# SCH_Bluetonium-canister_2024-05-14.net
KiCad netlist of a schematic drawn in EasyEDA
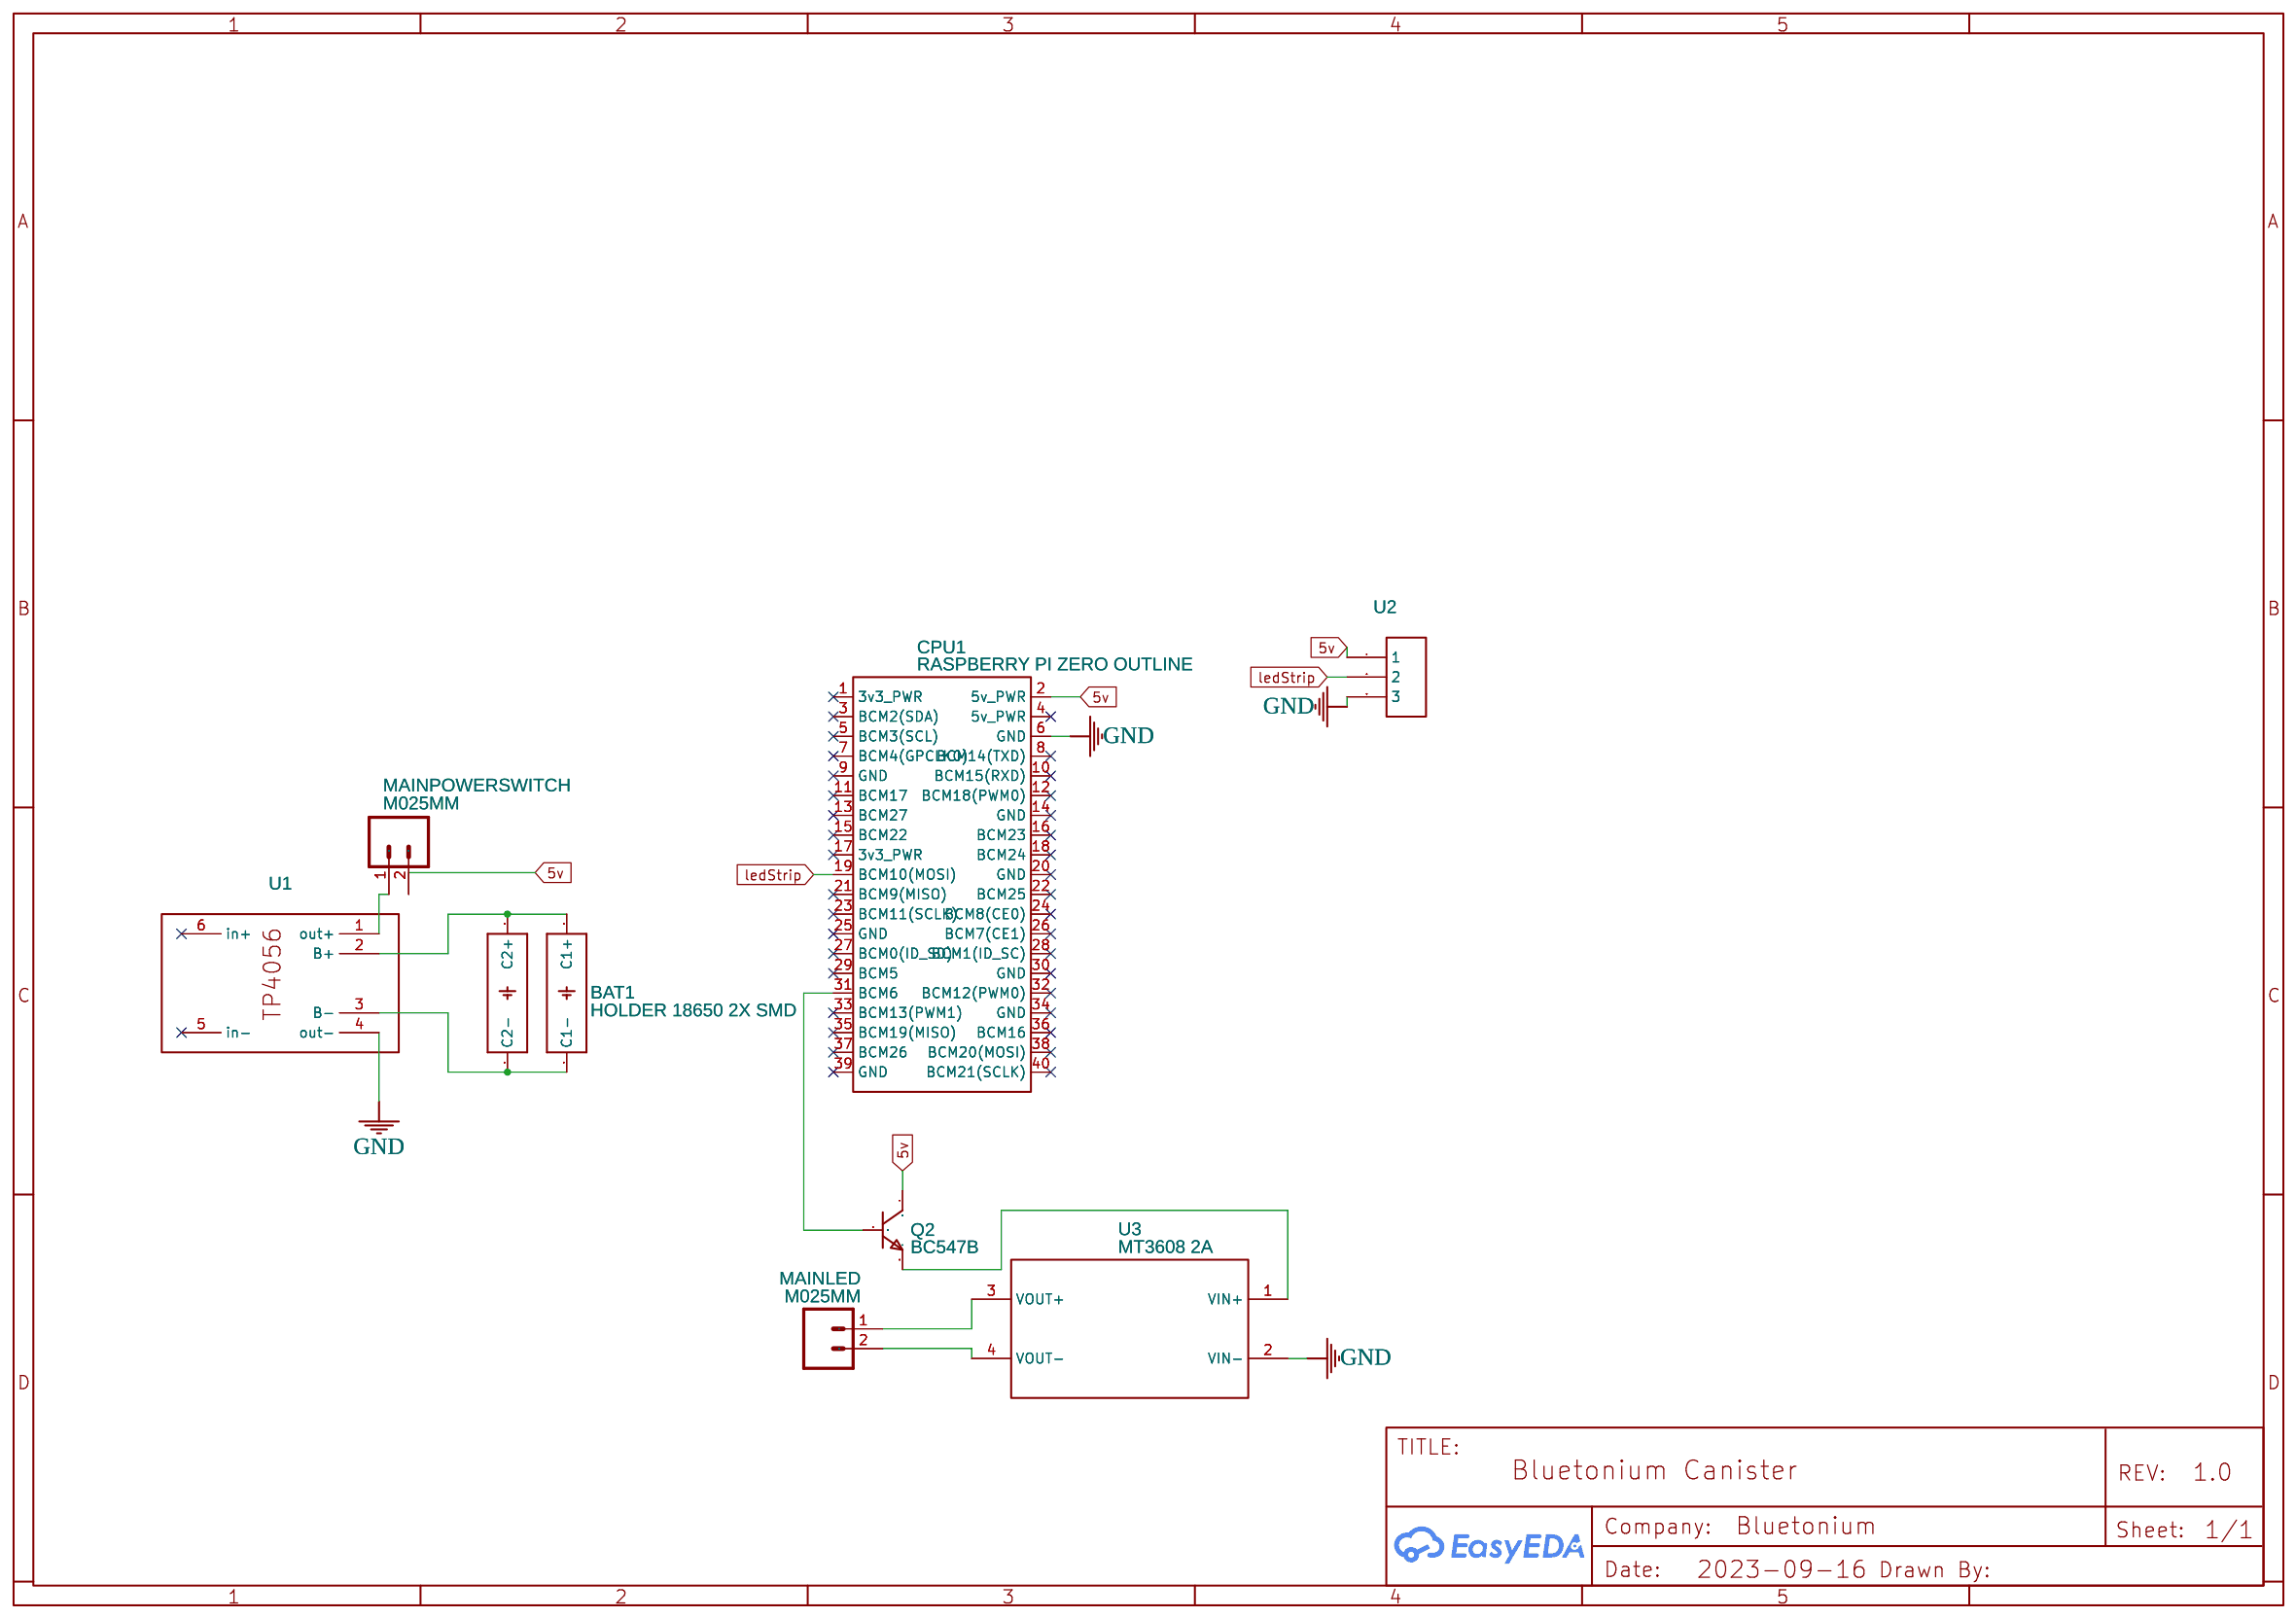
[diagram p0: schematic sheet]

(export (version "E")
  (design (tool "Eeschema 10.0.6"))
  (components
    (comp (ref "BAT1") (value "HOLDER 18650 2X SMD") (libsource (lib "") (part "HOLDER 18650 2X SMD")))
    (comp (ref "CPU1")
      (value "RASPBERRY PI ZERO OUTLINE")
      (fields (field (name "Manufacturer Part") "Pi Zero W") (field (name "Manufacturer") "Raspberry Pi"))
      (libsource (lib "") (part "RASPBERRY PI ZERO OUTLINE"))
    )
    (comp (ref "MAINLED") (value "M025MM") (libsource (lib "") (part "M025MM")))
    (comp (ref "MAINPOWERSWITCH") (value "M025MM") (libsource (lib "") (part "M025MM_1")))
    (comp (ref "Q2")
      (value "BC547B")
      (fields (field (name "Manufacturer") "MULTICOMP"))
      (libsource (lib "") (part "BC547B"))
    )
    (comp (ref "U1") (value "NO") (libsource (lib "") (part "TP4056")))
    (comp (ref "U2") (value "NO") (libsource (lib "") (part "PORT-3PIN-P2.54")))
    (comp (ref "U3")
      (value "MT3608 2A")
      (fields (field (name "Manufacturer Part") "mt3608-1"))
      (libsource (lib "") (part "MT3608 2A"))
    )
  )
  (nets
    (net (code "1") (name "5v") (class "Default")
      (node (ref "CPU1") (pin "2") (pinfunction "5v_PWR_2") (pintype "unspecified"))
      (node (ref "MAINPOWERSWITCH") (pin "2") (pinfunction "2_2") (pintype "bidirectional"))
      (node (ref "Q2") (pin "1") (pinfunction "C_1") (pintype "unspecified"))
      (node (ref "U2") (pin "1") (pinfunction "1_1") (pintype "unspecified"))
    )
    (net (code "2") (name "GND") (class "Default")
      (node (ref "CPU1") (pin "6") (pinfunction "GND_6") (pintype "unspecified"))
      (node (ref "U1") (pin "4") (pinfunction "out-_4") (pintype "unspecified"))
      (node (ref "U2") (pin "3") (pinfunction "3_3") (pintype "unspecified"))
      (node (ref "U3") (pin "2") (pinfunction "VIN-_2") (pintype "unspecified"))
    )
    (net (code "3") (name "Net-(BAT1-C1+)") (class "Default")
      (node (ref "BAT1") (pin "1+") (pinfunction "C1+_1+") (pintype "bidirectional"))
      (node (ref "BAT1") (pin "2+") (pinfunction "C2+_2+") (pintype "bidirectional"))
      (node (ref "U1") (pin "2") (pinfunction "B+_2") (pintype "unspecified"))
    )
    (net (code "4") (name "Net-(BAT1-C1-)") (class "Default")
      (node (ref "BAT1") (pin "1-") (pinfunction "C1-_1-") (pintype "bidirectional"))
      (node (ref "BAT1") (pin "2-") (pinfunction "C2-_2-") (pintype "bidirectional"))
      (node (ref "U1") (pin "3") (pinfunction "B-_3") (pintype "unspecified"))
    )
    (net (code "5") (name "Net-(CPU1-BCM6)") (class "Default")
      (node (ref "CPU1") (pin "31") (pinfunction "BCM6_31") (pintype "unspecified"))
      (node (ref "Q2") (pin "2") (pinfunction "B_2") (pintype "unspecified"))
    )
    (net (code "6") (name "Net-(Q2-E)") (class "Default")
      (node (ref "Q2") (pin "3") (pinfunction "E_3") (pintype "unspecified"))
      (node (ref "U3") (pin "1") (pinfunction "VIN+_1") (pintype "unspecified"))
    )
    (net (code "7") (name "Net-(U1-out+)") (class "Default")
      (node (ref "MAINPOWERSWITCH") (pin "1") (pinfunction "1_1") (pintype "bidirectional"))
      (node (ref "U1") (pin "1") (pinfunction "out+_1") (pintype "unspecified"))
    )
    (net (code "8") (name "Net-(U3-VOUT+)") (class "Default")
      (node (ref "MAINLED") (pin "1") (pinfunction "1_1") (pintype "bidirectional"))
      (node (ref "U3") (pin "3") (pinfunction "VOUT+_3") (pintype "unspecified"))
    )
    (net (code "9") (name "Net-(U3-VOUT-)") (class "Default")
      (node (ref "MAINLED") (pin "2") (pinfunction "2_2") (pintype "bidirectional"))
      (node (ref "U3") (pin "4") (pinfunction "VOUT-_4") (pintype "unspecified"))
    )
    (net (code "10") (name "ledStrip") (class "Default")
      (node (ref "CPU1") (pin "19") (pinfunction "BCM10(MOSI)_19") (pintype "unspecified"))
      (node (ref "U2") (pin "2") (pinfunction "2_2") (pintype "unspecified"))
    )
    (net (code "11") (name "unconnected-(CPU1-3v3_PWR-Pad1)") (class "Default")
      (node (ref "CPU1") (pin "1") (pinfunction "3v3_PWR_1") (pintype "passive+no_connect"))
    )
    (net (code "12") (name "unconnected-(CPU1-3v3_PWR-Pad17)") (class "Default")
      (node (ref "CPU1") (pin "17") (pinfunction "3v3_PWR_17") (pintype "unspecified+no_connect"))
    )
    (net (code "13") (name "unconnected-(CPU1-5v_PWR-Pad4)") (class "Default")
      (node (ref "CPU1") (pin "4") (pinfunction "5v_PWR_4") (pintype "unspecified+no_connect"))
    )
    (net (code "14") (name "unconnected-(CPU1-BCM0(ID_SD)-Pad27)") (class "Default")
      (node (ref "CPU1") (pin "27") (pinfunction "BCM0(ID_SD)_27") (pintype "unspecified+no_connect"))
    )
    (net (code "15") (name "unconnected-(CPU1-BCM1(ID_SC)-Pad28)") (class "Default")
      (node (ref "CPU1") (pin "28") (pinfunction "BCM1(ID_SC)_28") (pintype "unspecified+no_connect"))
    )
    (net (code "16") (name "unconnected-(CPU1-BCM2(SDA)-Pad3)") (class "Default")
      (node (ref "CPU1") (pin "3") (pinfunction "BCM2(SDA)_3") (pintype "unspecified+no_connect"))
    )
    (net (code "17") (name "unconnected-(CPU1-BCM3(SCL)-Pad5)") (class "Default")
      (node (ref "CPU1") (pin "5") (pinfunction "BCM3(SCL)_5") (pintype "unspecified+no_connect"))
    )
    (net (code "18") (name "unconnected-(CPU1-BCM4(GPCLK0)-Pad7)") (class "Default")
      (node (ref "CPU1") (pin "7") (pinfunction "BCM4(GPCLK0)_7") (pintype "unspecified+no_connect"))
    )
    (net (code "19") (name "unconnected-(CPU1-BCM5-Pad29)") (class "Default")
      (node (ref "CPU1") (pin "29") (pinfunction "BCM5_29") (pintype "unspecified+no_connect"))
    )
    (net (code "20") (name "unconnected-(CPU1-BCM7(CE1)-Pad26)") (class "Default")
      (node (ref "CPU1") (pin "26") (pinfunction "BCM7(CE1)_26") (pintype "unspecified+no_connect"))
    )
    (net (code "21") (name "unconnected-(CPU1-BCM8(CE0)-Pad24)") (class "Default")
      (node (ref "CPU1") (pin "24") (pinfunction "BCM8(CE0)_24") (pintype "unspecified+no_connect"))
    )
    (net (code "22") (name "unconnected-(CPU1-BCM9(MISO)-Pad21)") (class "Default")
      (node (ref "CPU1") (pin "21") (pinfunction "BCM9(MISO)_21") (pintype "unspecified+no_connect"))
    )
    (net (code "23") (name "unconnected-(CPU1-BCM11(SCLK)-Pad23)") (class "Default")
      (node (ref "CPU1") (pin "23") (pinfunction "BCM11(SCLK)_23") (pintype "unspecified+no_connect"))
    )
    (net (code "24") (name "unconnected-(CPU1-BCM12(PWM0)-Pad32)") (class "Default")
      (node (ref "CPU1") (pin "32") (pinfunction "BCM12(PWM0)_32") (pintype "unspecified+no_connect"))
    )
    (net (code "25") (name "unconnected-(CPU1-BCM13(PWM1)-Pad33)") (class "Default")
      (node (ref "CPU1") (pin "33") (pinfunction "BCM13(PWM1)_33") (pintype "unspecified+no_connect"))
    )
    (net (code "26") (name "unconnected-(CPU1-BCM14(TXD)-Pad8)") (class "Default")
      (node (ref "CPU1") (pin "8") (pinfunction "BCM14(TXD)_8") (pintype "unspecified+no_connect"))
    )
    (net (code "27") (name "unconnected-(CPU1-BCM15(RXD)-Pad10)") (class "Default")
      (node (ref "CPU1") (pin "10") (pinfunction "BCM15(RXD)_10") (pintype "unspecified+no_connect"))
    )
    (net (code "28") (name "unconnected-(CPU1-BCM16-Pad36)") (class "Default")
      (node (ref "CPU1") (pin "36") (pinfunction "BCM16_36") (pintype "unspecified+no_connect"))
    )
    (net (code "29") (name "unconnected-(CPU1-BCM17-Pad11)") (class "Default")
      (node (ref "CPU1") (pin "11") (pinfunction "BCM17_11") (pintype "unspecified+no_connect"))
    )
    (net (code "30") (name "unconnected-(CPU1-BCM18(PWM0)-Pad12)") (class "Default")
      (node (ref "CPU1") (pin "12") (pinfunction "BCM18(PWM0)_12") (pintype "unspecified+no_connect"))
    )
    (net (code "31") (name "unconnected-(CPU1-BCM19(MISO)-Pad35)") (class "Default")
      (node (ref "CPU1") (pin "35") (pinfunction "BCM19(MISO)_35") (pintype "unspecified+no_connect"))
    )
    (net (code "32") (name "unconnected-(CPU1-BCM20(MOSI)-Pad38)") (class "Default")
      (node (ref "CPU1") (pin "38") (pinfunction "BCM20(MOSI)_38") (pintype "unspecified+no_connect"))
    )
    (net (code "33") (name "unconnected-(CPU1-BCM21(SCLK)-Pad40)") (class "Default")
      (node (ref "CPU1") (pin "40") (pinfunction "BCM21(SCLK)_40") (pintype "unspecified+no_connect"))
    )
    (net (code "34") (name "unconnected-(CPU1-BCM22-Pad15)") (class "Default")
      (node (ref "CPU1") (pin "15") (pinfunction "BCM22_15") (pintype "unspecified+no_connect"))
    )
    (net (code "35") (name "unconnected-(CPU1-BCM23-Pad16)") (class "Default")
      (node (ref "CPU1") (pin "16") (pinfunction "BCM23_16") (pintype "unspecified+no_connect"))
    )
    (net (code "36") (name "unconnected-(CPU1-BCM24-Pad18)") (class "Default")
      (node (ref "CPU1") (pin "18") (pinfunction "BCM24_18") (pintype "unspecified+no_connect"))
    )
    (net (code "37") (name "unconnected-(CPU1-BCM25-Pad22)") (class "Default")
      (node (ref "CPU1") (pin "22") (pinfunction "BCM25_22") (pintype "unspecified+no_connect"))
    )
    (net (code "38") (name "unconnected-(CPU1-BCM26-Pad37)") (class "Default")
      (node (ref "CPU1") (pin "37") (pinfunction "BCM26_37") (pintype "unspecified+no_connect"))
    )
    (net (code "39") (name "unconnected-(CPU1-BCM27-Pad13)") (class "Default")
      (node (ref "CPU1") (pin "13") (pinfunction "BCM27_13") (pintype "unspecified+no_connect"))
    )
    (net (code "40") (name "unconnected-(CPU1-GND-Pad9)") (class "Default")
      (node (ref "CPU1") (pin "9") (pinfunction "GND_9") (pintype "unspecified+no_connect"))
    )
    (net (code "41") (name "unconnected-(CPU1-GND-Pad14)") (class "Default")
      (node (ref "CPU1") (pin "14") (pinfunction "GND_14") (pintype "unspecified+no_connect"))
    )
    (net (code "42") (name "unconnected-(CPU1-GND-Pad20)") (class "Default")
      (node (ref "CPU1") (pin "20") (pinfunction "GND_20") (pintype "unspecified+no_connect"))
    )
    (net (code "43") (name "unconnected-(CPU1-GND-Pad25)") (class "Default")
      (node (ref "CPU1") (pin "25") (pinfunction "GND_25") (pintype "unspecified+no_connect"))
    )
    (net (code "44") (name "unconnected-(CPU1-GND-Pad30)") (class "Default")
      (node (ref "CPU1") (pin "30") (pinfunction "GND_30") (pintype "unspecified+no_connect"))
    )
    (net (code "45") (name "unconnected-(CPU1-GND-Pad34)") (class "Default")
      (node (ref "CPU1") (pin "34") (pinfunction "GND_34") (pintype "unspecified+no_connect"))
    )
    (net (code "46") (name "unconnected-(CPU1-GND-Pad39)") (class "Default")
      (node (ref "CPU1") (pin "39") (pinfunction "GND_39") (pintype "unspecified+no_connect"))
    )
    (net (code "47") (name "unconnected-(U1-in+-Pad6)") (class "Default")
      (node (ref "U1") (pin "6") (pinfunction "in+_6") (pintype "unspecified+no_connect"))
    )
    (net (code "48") (name "unconnected-(U1-in--Pad5)") (class "Default")
      (node (ref "U1") (pin "5") (pinfunction "in-_5") (pintype "unspecified+no_connect"))
    )
  )
)
